# Main.net
KiCad netlist of a schematic drawn in Altium Designer
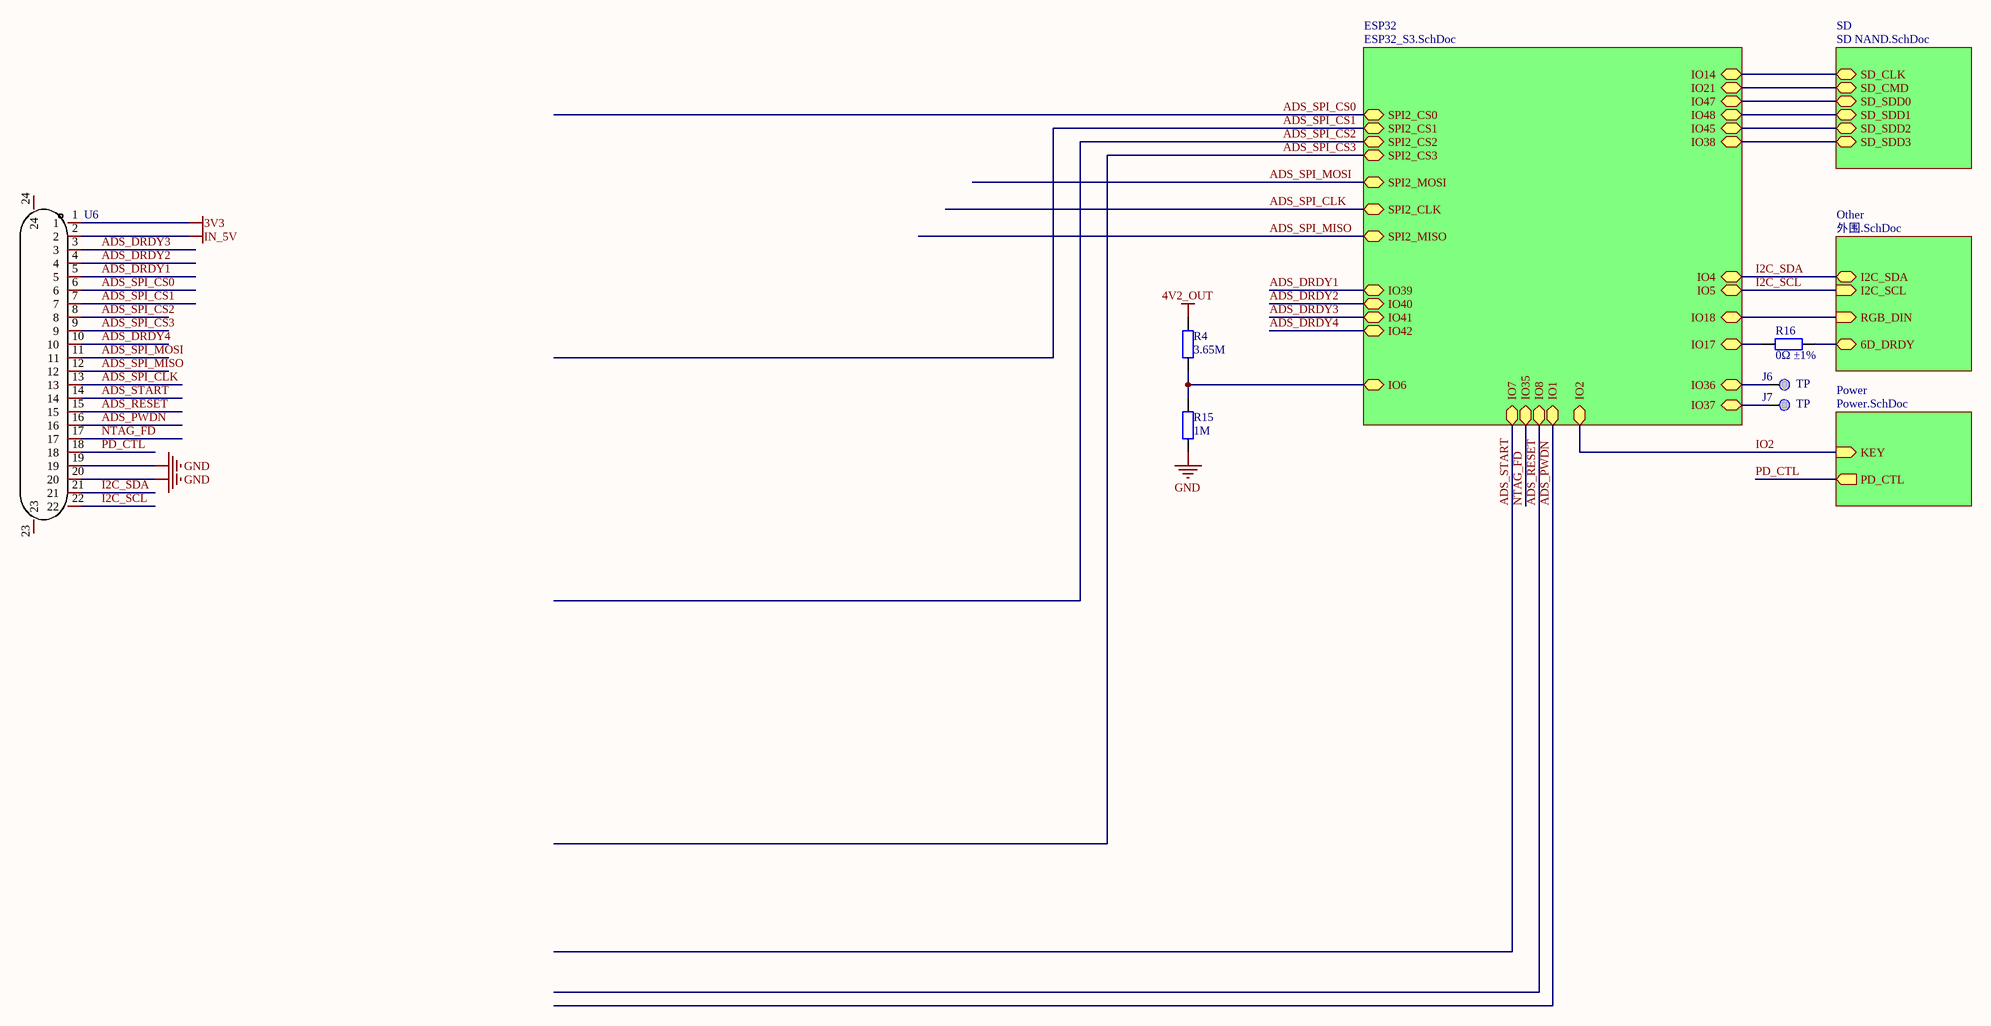
[diagram p0: Main.SchDoc]

(export (version "E")
  (design (tool "Eeschema 10.0.6"))
  (components
    (comp (ref "J6") (value "TP") (footprint "TEST_Point") (libsource (lib "RFID") (part "TestPad")))
    (comp (ref "J7") (value "TP") (footprint "TEST_Point") (libsource (lib "RFID") (part "TestPad")))
    (comp (ref "R4")
      (value "3.65M")
      (footprint "0603_R")
      (description "Resistor")
      (libsource (lib "Miscellaneous Devices") (part "Res2"))
    )
    (comp (ref "R15")
      (value "1M")
      (footprint "0603_R")
      (description "Resistor")
      (libsource (lib "Miscellaneous Devices") (part "Res2"))
    )
    (comp (ref "R16")
      (value "0Ω ±1%")
      (footprint "0402_R")
      (description "Resistor")
      (libsource (lib "") (part "Res2_1"))
    )
    (comp (ref "U6")
      (value "KH-FPC0.5-H1.0SMT-22P-QCHF")
      (footprint "FPC-SMD_22P-P0.50_XKB_X05A10L22G")
      (description "锁定特性:翻盖式;触点数量:22P;间距:0.5mm;")
      (fields (field (name "MANUFACTURER") "kinghelm(金航标)"))
      (libsource (lib "altium-import") (part "root_0_mirrored_KH-FPC0.5-H1.0SMT-22P-QCHF_"))
    )
  )
  (nets
    (net (code "1") (name "/6D_DRDY") (class "Default")
      (node (ref "R16") (pin "2") (pinfunction "2_2") (pintype "passive"))
    )
    (net (code "2") (name "/ADS_DRDY1") (class "Default")
      (node (ref "U6") (pin "5") (pinfunction "5_5") (pintype "passive"))
    )
    (net (code "3") (name "/ADS_DRDY2") (class "Default")
      (node (ref "U6") (pin "4") (pinfunction "4_4") (pintype "passive"))
    )
    (net (code "4") (name "/ADS_DRDY3") (class "Default")
      (node (ref "U6") (pin "3") (pinfunction "3_3") (pintype "passive"))
    )
    (net (code "5") (name "/ADS_DRDY4") (class "Default")
      (node (ref "U6") (pin "10") (pinfunction "10_10") (pintype "passive"))
    )
    (net (code "6") (name "/ADS_PWDN") (class "Default")
      (node (ref "U6") (pin "16") (pinfunction "16_16") (pintype "passive"))
    )
    (net (code "7") (name "/ADS_RESET") (class "Default")
      (node (ref "U6") (pin "15") (pinfunction "15_15") (pintype "passive"))
    )
    (net (code "8") (name "/ADS_SPI_CLK") (class "Default")
      (node (ref "U6") (pin "13") (pinfunction "13_13") (pintype "passive"))
    )
    (net (code "9") (name "/ADS_SPI_CS0") (class "Default")
      (node (ref "U6") (pin "6") (pinfunction "6_6") (pintype "passive"))
    )
    (net (code "10") (name "/ADS_SPI_CS1") (class "Default")
      (node (ref "U6") (pin "7") (pinfunction "7_7") (pintype "passive"))
    )
    (net (code "11") (name "/ADS_SPI_CS2") (class "Default")
      (node (ref "U6") (pin "8") (pinfunction "8_8") (pintype "passive"))
    )
    (net (code "12") (name "/ADS_SPI_CS3") (class "Default")
      (node (ref "U6") (pin "9") (pinfunction "9_9") (pintype "passive"))
    )
    (net (code "13") (name "/ADS_SPI_MISO") (class "Default")
      (node (ref "U6") (pin "12") (pinfunction "12_12") (pintype "passive"))
    )
    (net (code "14") (name "/ADS_SPI_MOSI") (class "Default")
      (node (ref "U6") (pin "11") (pinfunction "11_11") (pintype "passive"))
    )
    (net (code "15") (name "/ADS_START") (class "Default")
      (node (ref "U6") (pin "14") (pinfunction "14_14") (pintype "passive"))
    )
    (net (code "16") (name "/I2C_SCL") (class "Default")
      (node (ref "U6") (pin "22") (pinfunction "22_22") (pintype "passive"))
    )
    (net (code "17") (name "/I2C_SDA") (class "Default")
      (node (ref "U6") (pin "21") (pinfunction "21_21") (pintype "passive"))
    )
    (net (code "19") (name "/IO6") (class "Default")
      (node (ref "R15") (pin "1") (pinfunction "1_1") (pintype "passive"))
      (node (ref "R4") (pin "2") (pinfunction "2_2") (pintype "passive"))
    )
    (net (code "21") (name "/IO17") (class "Default")
      (node (ref "R16") (pin "1") (pinfunction "1_1") (pintype "passive"))
    )
    (net (code "24") (name "/IO36") (class "Default")
      (node (ref "J6") (pin "1") (pinfunction "1_1") (pintype "power_in"))
    )
    (net (code "25") (name "/IO37") (class "Default")
      (node (ref "J7") (pin "1") (pinfunction "1_1") (pintype "power_in"))
    )
    (net (code "30") (name "/NTAG_FD") (class "Default")
      (node (ref "U6") (pin "17") (pinfunction "17_17") (pintype "passive"))
    )
    (net (code "31") (name "/PD_CTL") (class "Default")
      (node (ref "U6") (pin "18") (pinfunction "18_18") (pintype "passive"))
    )
    (net (code "32") (name "3V3") (class "Default")
      (node (ref "U6") (pin "1") (pinfunction "1_1") (pintype "passive"))
    )
    (net (code "33") (name "4V2_OUT") (class "Default")
      (node (ref "R4") (pin "1") (pinfunction "1_1") (pintype "passive"))
    )
    (net (code "34") (name "GND") (class "Default")
      (node (ref "R15") (pin "2") (pinfunction "2_2") (pintype "passive"))
      (node (ref "U6") (pin "19") (pinfunction "19_19") (pintype "passive"))
      (node (ref "U6") (pin "20") (pinfunction "20_20") (pintype "passive"))
    )
    (net (code "35") (name "IN_5V") (class "Default")
      (node (ref "U6") (pin "2") (pinfunction "2_2") (pintype "passive"))
    )
    (net (code "36") (name "unconnected-(U6-Pad23)") (class "Default")
      (node (ref "U6") (pin "23") (pinfunction "23_23") (pintype "passive"))
    )
    (net (code "37") (name "unconnected-(U6-Pad24)") (class "Default")
      (node (ref "U6") (pin "24") (pinfunction "24_24") (pintype "passive"))
    )
  )
)
